# leddriver.net
KiCad netlist of a schematic drawn in Altium Designer
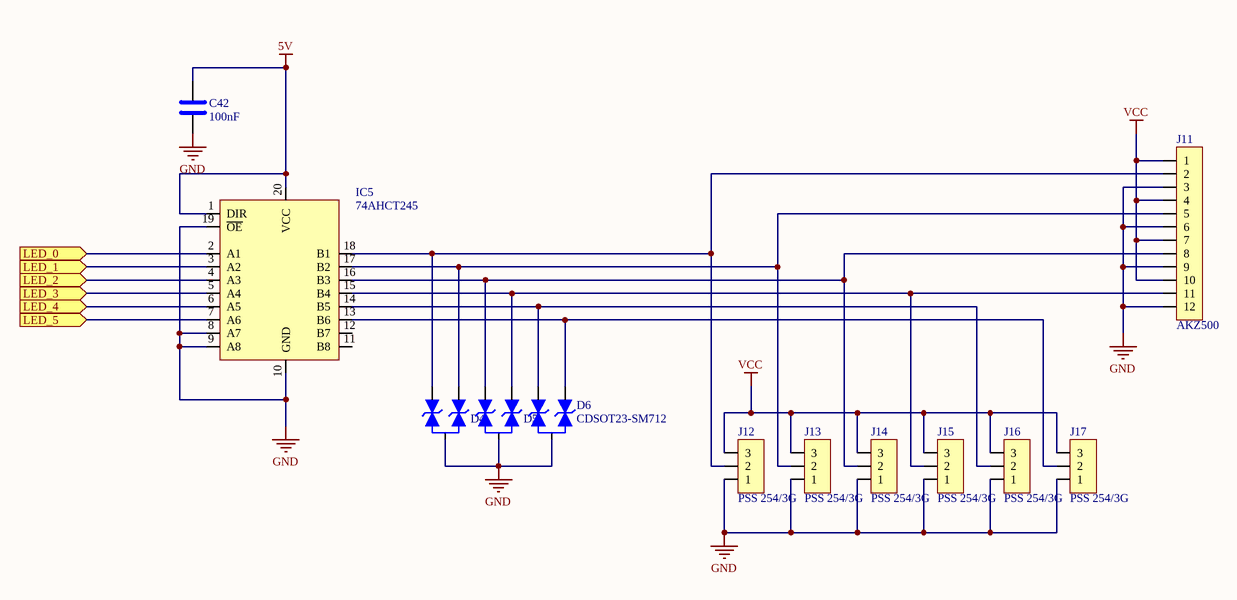
[diagram p0: leddriver.SchDoc]

(export (version "E")
  (design (tool "Eeschema 10.0.6"))
  (components
    (comp (ref "C42")
      (value "100nF")
      (footprint "0603")
      (description "100nF 50V MLCC 0603")
      (fields (field (name "VOLTAGE") "50V"))
      (libsource (lib "capacitors") (part "100nF 50V MLCC 0603"))
    )
    (comp (ref "D4")
      (value "CDSOT23-SM712")
      (footprint "SOT23")
      (description "Dual TVS diode")
      (libsource (lib "diodes") (part "CDSOT23-SM712"))
    )
    (comp (ref "D5")
      (value "CDSOT23-SM712")
      (footprint "SOT23")
      (description "Dual TVS diode")
      (libsource (lib "diodes") (part "CDSOT23-SM712"))
    )
    (comp (ref "D6")
      (value "CDSOT23-SM712")
      (footprint "SOT23")
      (description "Dual TVS diode")
      (libsource (lib "diodes") (part "CDSOT23-SM712"))
    )
    (comp (ref "IC5")
      (value "74AHCT245")
      (footprint "TSSOP20")
      (description "Octal Tristate Bus driver")
      (libsource (lib "misc") (part "SN74AHCT245"))
    )
    (comp (ref "J11")
      (value "AKZ500")
      (footprint "AKZ500/12")
      (libsource (lib "connectors_screw") (part "AKZ500/12"))
    )
    (comp (ref "J12")
      (value "PSS 254/3G")
      (footprint "PSS 3pol")
      (description "PSS 3pol wire-to-board-connector")
      (libsource (lib "connectors_pss") (part "PSS 254/3G"))
    )
    (comp (ref "J13")
      (value "PSS 254/3G")
      (footprint "PSS 3pol")
      (description "PSS 3pol wire-to-board-connector")
      (libsource (lib "connectors_pss") (part "PSS 254/3G"))
    )
    (comp (ref "J14")
      (value "PSS 254/3G")
      (footprint "PSS 3pol")
      (description "PSS 3pol wire-to-board-connector")
      (libsource (lib "connectors_pss") (part "PSS 254/3G"))
    )
    (comp (ref "J15")
      (value "PSS 254/3G")
      (footprint "PSS 3pol")
      (description "PSS 3pol wire-to-board-connector")
      (libsource (lib "connectors_pss") (part "PSS 254/3G"))
    )
    (comp (ref "J16")
      (value "PSS 254/3G")
      (footprint "PSS 3pol")
      (description "PSS 3pol wire-to-board-connector")
      (libsource (lib "connectors_pss") (part "PSS 254/3G"))
    )
    (comp (ref "J17")
      (value "PSS 254/3G")
      (footprint "PSS 3pol")
      (description "PSS 3pol wire-to-board-connector")
      (libsource (lib "connectors_pss") (part "PSS 254/3G"))
    )
  )
  (nets
    (net (code "1") (name "/LED_0") (class "Default")
      (node (ref "IC5") (pin "2") (pinfunction "A1_2") (pintype "passive"))
    )
    (net (code "2") (name "/LED_1") (class "Default")
      (node (ref "IC5") (pin "3") (pinfunction "A2_3") (pintype "passive"))
    )
    (net (code "3") (name "/LED_2") (class "Default")
      (node (ref "IC5") (pin "4") (pinfunction "A3_4") (pintype "passive"))
    )
    (net (code "4") (name "/LED_3") (class "Default")
      (node (ref "IC5") (pin "5") (pinfunction "A4_5") (pintype "passive"))
    )
    (net (code "5") (name "/LED_4") (class "Default")
      (node (ref "IC5") (pin "6") (pinfunction "A5_6") (pintype "passive"))
    )
    (net (code "6") (name "/LED_5") (class "Default")
      (node (ref "IC5") (pin "7") (pinfunction "A6_7") (pintype "passive"))
    )
    (net (code "7") (name "5V") (class "Default")
      (node (ref "C42") (pin "1") (pinfunction "1_1") (pintype "passive"))
      (node (ref "IC5") (pin "1") (pinfunction "DIR_1") (pintype "passive"))
      (node (ref "IC5") (pin "20") (pinfunction "VCC_20") (pintype "passive"))
    )
    (net (code "8") (name "GND") (class "Default")
      (node (ref "C42") (pin "2") (pinfunction "2_2") (pintype "passive"))
      (node (ref "D4") (pin "3") (pinfunction "3_3") (pintype "passive"))
      (node (ref "D5") (pin "3") (pinfunction "3_3") (pintype "passive"))
      (node (ref "D6") (pin "3") (pinfunction "3_3") (pintype "passive"))
      (node (ref "IC5") (pin "10") (pinfunction "GND_10") (pintype "passive"))
      (node (ref "IC5") (pin "19") (pinfunction "~{OE}_19") (pintype "passive"))
      (node (ref "IC5") (pin "8") (pinfunction "A7_8") (pintype "passive"))
      (node (ref "IC5") (pin "9") (pinfunction "A8_9") (pintype "passive"))
      (node (ref "J11") (pin "12") (pinfunction "12_12") (pintype "passive"))
      (node (ref "J11") (pin "3") (pinfunction "3_3") (pintype "passive"))
      (node (ref "J11") (pin "6") (pinfunction "6_6") (pintype "passive"))
      (node (ref "J11") (pin "9") (pinfunction "9_9") (pintype "passive"))
      (node (ref "J12") (pin "1") (pinfunction "1_1") (pintype "passive"))
      (node (ref "J13") (pin "1") (pinfunction "1_1") (pintype "passive"))
      (node (ref "J14") (pin "1") (pinfunction "1_1") (pintype "passive"))
      (node (ref "J15") (pin "1") (pinfunction "1_1") (pintype "passive"))
      (node (ref "J16") (pin "1") (pinfunction "1_1") (pintype "passive"))
      (node (ref "J17") (pin "1") (pinfunction "1_1") (pintype "passive"))
    )
    (net (code "9") (name "Net-(IC5-B1)") (class "Default")
      (node (ref "D4") (pin "1") (pinfunction "1_1") (pintype "passive"))
      (node (ref "IC5") (pin "18") (pinfunction "B1_18") (pintype "passive"))
      (node (ref "J11") (pin "2") (pinfunction "2_2") (pintype "passive"))
      (node (ref "J12") (pin "2") (pinfunction "2_2") (pintype "passive"))
    )
    (net (code "10") (name "Net-(IC5-B2)") (class "Default")
      (node (ref "D4") (pin "2") (pinfunction "2_2") (pintype "passive"))
      (node (ref "IC5") (pin "17") (pinfunction "B2_17") (pintype "passive"))
      (node (ref "J11") (pin "5") (pinfunction "5_5") (pintype "passive"))
      (node (ref "J13") (pin "2") (pinfunction "2_2") (pintype "passive"))
    )
    (net (code "11") (name "Net-(IC5-B3)") (class "Default")
      (node (ref "D5") (pin "1") (pinfunction "1_1") (pintype "passive"))
      (node (ref "IC5") (pin "16") (pinfunction "B3_16") (pintype "passive"))
      (node (ref "J11") (pin "8") (pinfunction "8_8") (pintype "passive"))
      (node (ref "J14") (pin "2") (pinfunction "2_2") (pintype "passive"))
    )
    (net (code "12") (name "Net-(IC5-B4)") (class "Default")
      (node (ref "D5") (pin "2") (pinfunction "2_2") (pintype "passive"))
      (node (ref "IC5") (pin "15") (pinfunction "B4_15") (pintype "passive"))
      (node (ref "J11") (pin "11") (pinfunction "11_11") (pintype "passive"))
      (node (ref "J15") (pin "2") (pinfunction "2_2") (pintype "passive"))
    )
    (net (code "13") (name "Net-(IC5-B5)") (class "Default")
      (node (ref "D6") (pin "1") (pinfunction "1_1") (pintype "passive"))
      (node (ref "IC5") (pin "14") (pinfunction "B5_14") (pintype "passive"))
      (node (ref "J16") (pin "2") (pinfunction "2_2") (pintype "passive"))
    )
    (net (code "14") (name "Net-(IC5-B6)") (class "Default")
      (node (ref "D6") (pin "2") (pinfunction "2_2") (pintype "passive"))
      (node (ref "IC5") (pin "13") (pinfunction "B6_13") (pintype "passive"))
      (node (ref "J17") (pin "2") (pinfunction "2_2") (pintype "passive"))
    )
    (net (code "15") (name "VCC") (class "Default")
      (node (ref "J11") (pin "1") (pinfunction "1_1") (pintype "passive"))
      (node (ref "J11") (pin "10") (pinfunction "10_10") (pintype "passive"))
      (node (ref "J11") (pin "4") (pinfunction "4_4") (pintype "passive"))
      (node (ref "J11") (pin "7") (pinfunction "7_7") (pintype "passive"))
      (node (ref "J12") (pin "3") (pinfunction "3_3") (pintype "passive"))
      (node (ref "J13") (pin "3") (pinfunction "3_3") (pintype "passive"))
      (node (ref "J14") (pin "3") (pinfunction "3_3") (pintype "passive"))
      (node (ref "J15") (pin "3") (pinfunction "3_3") (pintype "passive"))
      (node (ref "J16") (pin "3") (pinfunction "3_3") (pintype "passive"))
      (node (ref "J17") (pin "3") (pinfunction "3_3") (pintype "passive"))
    )
    (net (code "16") (name "unconnected-(IC5-B7-Pad12)") (class "Default")
      (node (ref "IC5") (pin "12") (pinfunction "B7_12") (pintype "passive"))
    )
    (net (code "17") (name "unconnected-(IC5-B8-Pad11)") (class "Default")
      (node (ref "IC5") (pin "11") (pinfunction "B8_11") (pintype "passive"))
    )
  )
)
